# Placa_teste.net
KiCad netlist of a schematic drawn in Altium Designer
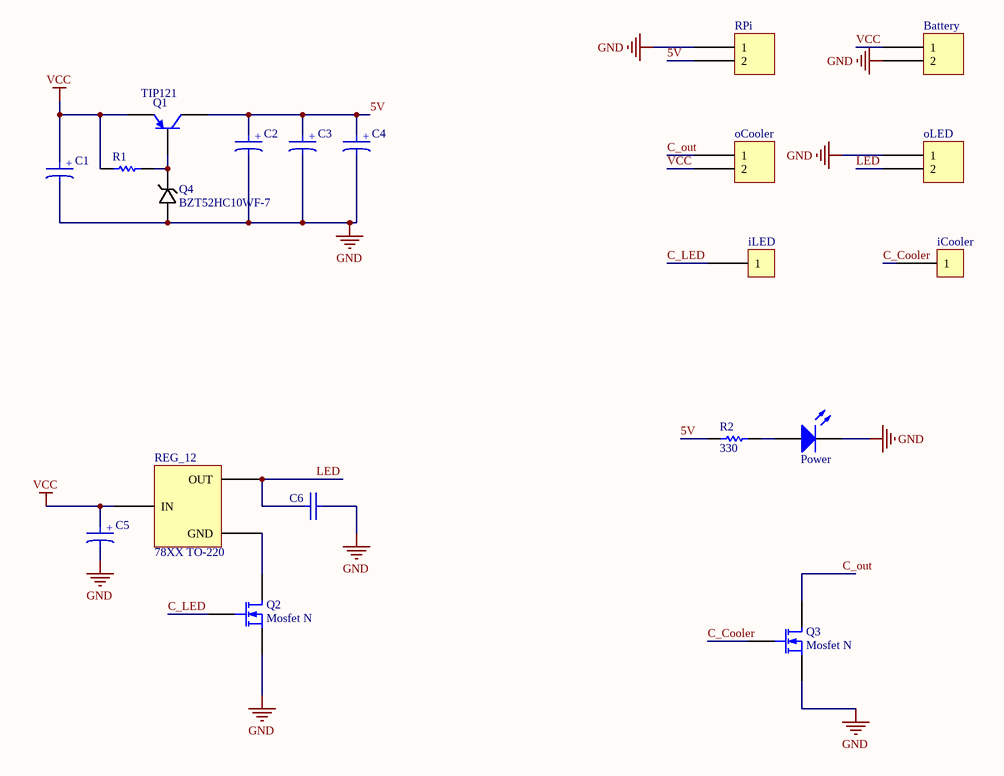
[diagram p0: Placa teste.SchDoc]

(export (version "E")
  (design (tool "Eeschema 10.0.6"))
  (components
    (comp (ref "Battery") (value "*") (footprint "XT90") (libsource (lib "Connectors") (part "XT90")))
    (comp (ref "C1")
      (value "*")
      (footprint "Eletrolytic Capacitor 5x5mm")
      (libsource (lib "Components") (part "Electrolytic Capacitor 0.33uF"))
    )
    (comp (ref "C2")
      (value "*")
      (footprint "Eletrolytic Capacitor 5x5mm")
      (libsource (lib "Components") (part "Electrolytic Capacitor 0.33uF"))
    )
    (comp (ref "C3")
      (value "*")
      (footprint "Eletrolytic Capacitor 5x5mm")
      (libsource (lib "Components") (part "Electrolytic Capacitor 0.33uF"))
    )
    (comp (ref "C4")
      (value "*")
      (footprint "Eletrolytic Capacitor 5x5mm")
      (libsource (lib "Components") (part "Electrolytic Capacitor 0.33uF"))
    )
    (comp (ref "C5")
      (value "*")
      (footprint "Eletrolytic Capacitor 5x5mm")
      (libsource (lib "Components") (part "Electrolytic Capacitor 0.33uF"))
    )
    (comp (ref "C6")
      (value "*")
      (footprint "SMD Capacitor")
      (libsource (lib "Components") (part "Capacitor SMD 0805"))
    )
    (comp (ref "iCooler")
      (value "*")
      (footprint "HEADER 1X1 8.5MM")
      (libsource (lib "Connectors") (part "Male Pin Head 1x1"))
    )
    (comp (ref "iLED")
      (value "*")
      (footprint "HEADER 1X1 8.5MM")
      (libsource (lib "Connectors") (part "Male Pin Head 1x1"))
    )
    (comp (ref "oCooler")
      (value "*")
      (footprint "KK2")
      (description "KK Connector, 2 ways")
      (libsource (lib "Connectors") (part "KK2"))
    )
    (comp (ref "oLED")
      (value "*")
      (footprint "KK2")
      (description "KK Connector, 2 ways")
      (libsource (lib "Connectors") (part "KK2"))
    )
    (comp (ref "Power")
      (value "LED 5mm THT")
      (footprint "LED THT")
      (libsource (lib "Components") (part "LED 5mm THT"))
    )
    (comp (ref "Q1")
      (value "TIP121")
      (footprint "TO-92A")
      (description "PNP General Purpose Amplifier")
      (fields (field (name "PUBLISHER") "Altium Limited"))
      (libsource (lib "Miscellaneous Devices") (part "2N3906"))
    )
    (comp (ref "Q2") (value "Mosfet N") (footprint "TO-220") (libsource (lib "Components") (part "Mosfet N")))
    (comp (ref "Q3") (value "Mosfet N") (footprint "TO-220") (libsource (lib "Components") (part "Mosfet N")))
    (comp (ref "Q4")
      (value "BZT52HC10WF-7")
      (footprint "SOD123")
      (description "Diode Zener 10.6V 375 mW AEC-Q101")
      (libsource (lib "Components") (part "BZT52HC10WF-7"))
    )
    (comp (ref "R1")
      (value "Resistor THT")
      (footprint "RESISTOR THT 5mm")
      (libsource (lib "Components") (part "Resistor THT"))
    )
    (comp (ref "R2")
      (value "330")
      (footprint "RESISTOR THT 5mm")
      (fields (field (name "Comment") "Resistor THT"))
      (libsource (lib "Components") (part "Resistor THT"))
    )
    (comp (ref "REG_12")
      (value "78XX TO-220")
      (footprint "TO-220")
      (libsource (lib "Components") (part "78XX TO-220"))
    )
    (comp (ref "RPi")
      (value "*")
      (footprint "KK2")
      (description "KK Connector, 2 ways")
      (libsource (lib "Connectors") (part "KK2"))
    )
  )
  (nets
    (net (code "1") (name "/5V") (class "Default")
      (node (ref "C2") (pin "1") (pintype "passive"))
      (node (ref "C3") (pin "1") (pintype "passive"))
      (node (ref "C4") (pin "1") (pintype "passive"))
      (node (ref "Q1") (pin "3") (pinfunction "C_3") (pintype "passive"))
      (node (ref "R2") (pin "1") (pinfunction "1_1") (pintype "passive"))
      (node (ref "RPi") (pin "2") (pinfunction "2_2") (pintype "passive"))
    )
    (net (code "2") (name "/C_Cooler") (class "Default")
      (node (ref "Q3") (pin "2") (pinfunction "G_2") (pintype "passive"))
      (node (ref "iCooler") (pin "1") (pinfunction "1_1") (pintype "passive"))
    )
    (net (code "3") (name "/C_LED") (class "Default")
      (node (ref "Q2") (pin "2") (pinfunction "G_2") (pintype "passive"))
      (node (ref "iLED") (pin "1") (pinfunction "1_1") (pintype "passive"))
    )
    (net (code "4") (name "/C_out") (class "Default")
      (node (ref "Q3") (pin "3") (pinfunction "D_3") (pintype "passive"))
      (node (ref "oCooler") (pin "1") (pinfunction "1_1") (pintype "passive"))
    )
    (net (code "5") (name "/LED") (class "Default")
      (node (ref "C6") (pin "2") (pintype "passive"))
      (node (ref "REG_12") (pin "3") (pinfunction "OUT_3") (pintype "passive"))
      (node (ref "oLED") (pin "2") (pinfunction "2_2") (pintype "passive"))
    )
    (net (code "6") (name "GND") (class "Default")
      (node (ref "Battery") (pin "2") (pinfunction "2_2") (pintype "passive"))
      (node (ref "C1") (pin "2") (pintype "passive"))
      (node (ref "C2") (pin "2") (pintype "passive"))
      (node (ref "C3") (pin "2") (pintype "passive"))
      (node (ref "C4") (pin "2") (pintype "passive"))
      (node (ref "C5") (pin "2") (pintype "passive"))
      (node (ref "C6") (pin "1") (pintype "passive"))
      (node (ref "Power") (pin "2") (pinfunction "K_2") (pintype "passive"))
      (node (ref "Q2") (pin "1") (pinfunction "S_1") (pintype "passive"))
      (node (ref "Q3") (pin "1") (pinfunction "S_1") (pintype "passive"))
      (node (ref "Q4") (pin "A") (pinfunction "A_A") (pintype "passive"))
      (node (ref "RPi") (pin "1") (pinfunction "1_1") (pintype "passive"))
      (node (ref "oLED") (pin "1") (pinfunction "1_1") (pintype "passive"))
    )
    (net (code "7") (name "Net-(Power-A)") (class "Default")
      (node (ref "Power") (pin "1") (pinfunction "A_1") (pintype "passive"))
      (node (ref "R2") (pin "2") (pinfunction "2_2") (pintype "passive"))
    )
    (net (code "8") (name "Net-(Q1-B)") (class "Default")
      (node (ref "Q1") (pin "2") (pinfunction "B_2") (pintype "passive"))
      (node (ref "Q4") (pin "K") (pinfunction "K_K") (pintype "passive"))
      (node (ref "R1") (pin "2") (pinfunction "2_2") (pintype "passive"))
    )
    (net (code "9") (name "Net-(Q2-D)") (class "Default")
      (node (ref "Q2") (pin "3") (pinfunction "D_3") (pintype "passive"))
      (node (ref "REG_12") (pin "2") (pinfunction "GND_2") (pintype "passive"))
    )
    (net (code "10") (name "VCC") (class "Default")
      (node (ref "Battery") (pin "1") (pinfunction "1_1") (pintype "passive"))
      (node (ref "C1") (pin "1") (pintype "passive"))
      (node (ref "C5") (pin "1") (pintype "passive"))
      (node (ref "Q1") (pin "1") (pinfunction "E_1") (pintype "passive"))
      (node (ref "R1") (pin "1") (pinfunction "1_1") (pintype "passive"))
      (node (ref "REG_12") (pin "1") (pinfunction "IN_1") (pintype "passive"))
      (node (ref "oCooler") (pin "2") (pinfunction "2_2") (pintype "passive"))
    )
  )
)
